# MiniBOT_New.net
KiCad netlist of a schematic drawn in EAGLE
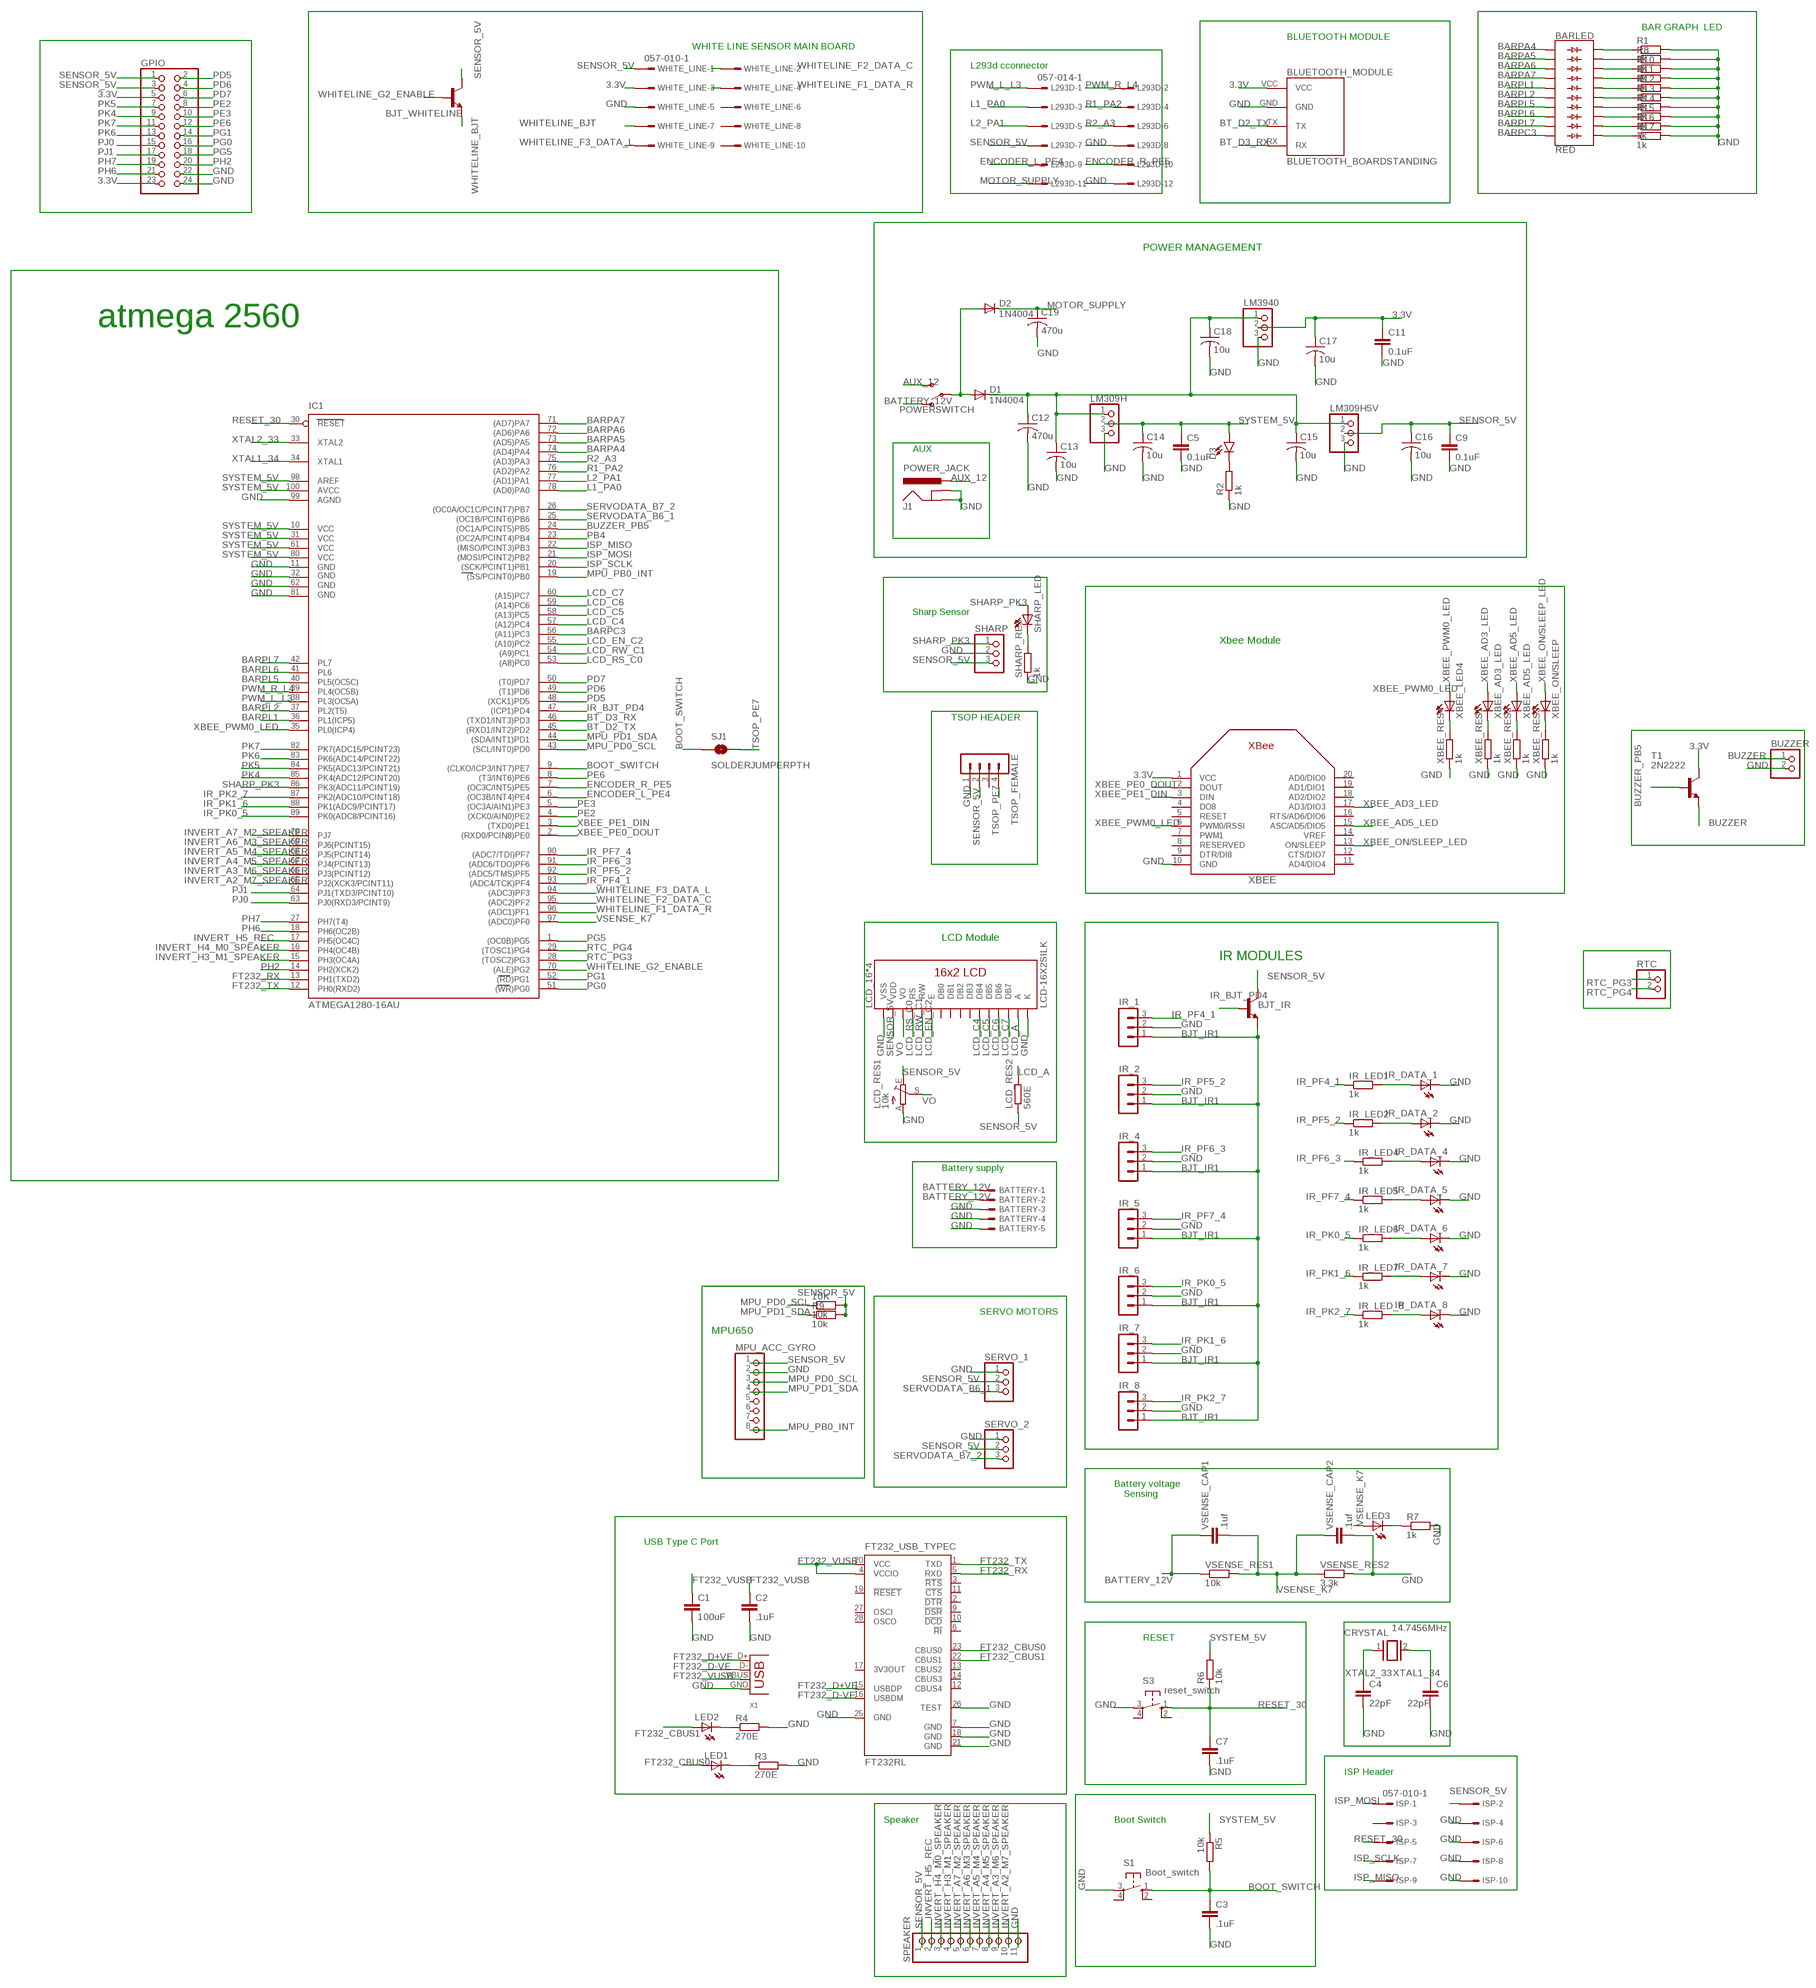
[diagram p0: schematic, sheet 1]

(export (version "E")
  (design (tool "Eeschema 10.0.6"))
  (components
    (comp (ref "10K")
      (value "10k")
      (footprint "eagle-import:R1206")
      (libsource (lib "eagle-import") (part "R-EU_R1206"))
    )
    (comp (ref "BARLED")
      (value "RED")
      (footprint "eagle-import:LED_BARGRAPH_10")
      (libsource (lib "eagle-import") (part "LED_BARGRAPH_10RED"))
    )
    (comp (ref "BATTERY")
      (value "KK-156-5")
      (footprint "eagle-import:KK-156-5")
      (libsource (lib "eagle-import") (part "KK-156-5"))
    )
    (comp (ref "BJT_IR")
      (value "2N2222")
      (footprint "eagle-import:TO92-EBC-OVAL")
      (libsource (lib "eagle-import") (part "2N2222"))
    )
    (comp (ref "BJT_WHITELINE")
      (value "2N2222")
      (footprint "eagle-import:TO92-EBC-OVAL")
      (libsource (lib "eagle-import") (part "2N2222"))
    )
    (comp (ref "BLUETOOTH_MODULE")
      (value "BLUETOOTH_BOARDSTANDING")
      (footprint "eagle-import:BT_BOARD_FOOTPRINT_STANDING")
      (libsource (lib "eagle-import") (part "BLUETOOTH_BOARDSTANDING"))
    )
    (comp (ref "BUZZER")
      (value "PINHD-1X2")
      (footprint "eagle-import:1X02")
      (libsource (lib "eagle-import") (part "PINHD-1X2"))
    )
    (comp (ref "C1")
      (value "100uF")
      (footprint "eagle-import:C1206")
      (libsource (lib "eagle-import") (part "C-EUC1206"))
    )
    (comp (ref "C2")
      (value ".1uF")
      (footprint "eagle-import:C1206")
      (libsource (lib "eagle-import") (part "C-EUC1206"))
    )
    (comp (ref "C3")
      (value ".1uF")
      (footprint "eagle-import:C1206")
      (libsource (lib "eagle-import") (part "C-EUC1206"))
    )
    (comp (ref "C4")
      (value "22pF")
      (footprint "eagle-import:C1206")
      (libsource (lib "eagle-import") (part "C-EUC1206"))
    )
    (comp (ref "C5")
      (value "0.1uF")
      (footprint "eagle-import:C1206")
      (libsource (lib "eagle-import") (part "C-EUC1206"))
    )
    (comp (ref "C6")
      (value "22pF")
      (footprint "eagle-import:C1206")
      (libsource (lib "eagle-import") (part "C-EUC1206"))
    )
    (comp (ref "C7")
      (value ".1uF")
      (footprint "eagle-import:C1206")
      (libsource (lib "eagle-import") (part "C-EUC1206"))
    )
    (comp (ref "C9")
      (value "0.1uF")
      (footprint "eagle-import:C1206")
      (libsource (lib "eagle-import") (part "C-EUC1206"))
    )
    (comp (ref "C11")
      (value "0.1uF")
      (footprint "eagle-import:C1206")
      (libsource (lib "eagle-import") (part "C-EUC1206"))
    )
    (comp (ref "C12")
      (value "470u")
      (footprint "eagle-import:C025-050X050")
      (libsource (lib "eagle-import") (part "C-US025-050X050"))
    )
    (comp (ref "C13")
      (value "10u")
      (footprint "eagle-import:C025-050X050")
      (libsource (lib "eagle-import") (part "C-US025-050X050"))
    )
    (comp (ref "C14")
      (value "10u")
      (footprint "eagle-import:C025-050X050")
      (libsource (lib "eagle-import") (part "C-US025-050X050"))
    )
    (comp (ref "C15")
      (value "10u")
      (footprint "eagle-import:C025-050X050")
      (libsource (lib "eagle-import") (part "C-US025-050X050"))
    )
    (comp (ref "C16")
      (value "10u")
      (footprint "eagle-import:C025-050X050")
      (libsource (lib "eagle-import") (part "C-US025-050X050"))
    )
    (comp (ref "C17")
      (value "10u")
      (footprint "eagle-import:C025-050X050")
      (libsource (lib "eagle-import") (part "C-US025-050X050"))
    )
    (comp (ref "C18")
      (value "10u")
      (footprint "eagle-import:C025-050X050")
      (libsource (lib "eagle-import") (part "C-US025-050X050"))
    )
    (comp (ref "C19")
      (value "470u")
      (footprint "eagle-import:C025-050X050")
      (libsource (lib "eagle-import") (part "C-US025-050X050"))
    )
    (comp (ref "CRYSTAL")
      (value "14.7456MHz")
      (footprint "eagle-import:QS")
      (libsource (lib "eagle-import") (part "XTAL/S"))
    )
    (comp (ref "D1")
      (value "1N4004")
      (footprint "eagle-import:DO41-10")
      (libsource (lib "eagle-import") (part "1N4004"))
    )
    (comp (ref "D2")
      (value "1N4004")
      (footprint "eagle-import:DO41-10")
      (libsource (lib "eagle-import") (part "1N4004"))
    )
    (comp (ref "D3")
      (value "LED1206")
      (footprint "eagle-import:LED-1206")
      (libsource (lib "eagle-import") (part "LED1206"))
    )
    (comp (ref "FT232_USB_TYPEC")
      (value "FT232RL")
      (footprint "eagle-import:SSOP28")
      (libsource (lib "eagle-import") (part "FT232RL"))
    )
    (comp (ref "GPIO")
      (value "PINHD-2X12")
      (footprint "eagle-import:2X12")
      (libsource (lib "eagle-import") (part "PINHD-2X12"))
    )
    (comp (ref "IC1")
      (value "ATMEGA1280-16AU")
      (footprint "eagle-import:TQFP100")
      (libsource (lib "eagle-import") (part "ATMEGAAU1280-16"))
    )
    (comp (ref "IR_1")
      (value "MA03-1")
      (footprint "eagle-import:MA03-1")
      (libsource (lib "eagle-import") (part "MA03-1"))
    )
    (comp (ref "IR_2")
      (value "MA03-1")
      (footprint "eagle-import:MA03-1")
      (libsource (lib "eagle-import") (part "MA03-1"))
    )
    (comp (ref "IR_4")
      (value "MA03-1")
      (footprint "eagle-import:MA03-1")
      (libsource (lib "eagle-import") (part "MA03-1"))
    )
    (comp (ref "IR_5")
      (value "MA03-1")
      (footprint "eagle-import:MA03-1")
      (libsource (lib "eagle-import") (part "MA03-1"))
    )
    (comp (ref "IR_6")
      (value "MA03-1")
      (footprint "eagle-import:MA03-1")
      (libsource (lib "eagle-import") (part "MA03-1"))
    )
    (comp (ref "IR_7")
      (value "MA03-1")
      (footprint "eagle-import:MA03-1")
      (libsource (lib "eagle-import") (part "MA03-1"))
    )
    (comp (ref "IR_8")
      (value "MA03-1")
      (footprint "eagle-import:MA03-1")
      (libsource (lib "eagle-import") (part "MA03-1"))
    )
    (comp (ref "IR_DATA_1")
      (value "LEDSMT1206")
      (footprint "eagle-import:1206")
      (libsource (lib "eagle-import") (part "LEDSMT1206"))
    )
    (comp (ref "IR_DATA_2")
      (value "LEDSMT1206")
      (footprint "eagle-import:1206")
      (libsource (lib "eagle-import") (part "LEDSMT1206"))
    )
    (comp (ref "IR_DATA_4")
      (value "LEDSMT1206")
      (footprint "eagle-import:1206")
      (libsource (lib "eagle-import") (part "LEDSMT1206"))
    )
    (comp (ref "IR_DATA_5")
      (value "LEDSMT1206")
      (footprint "eagle-import:1206")
      (libsource (lib "eagle-import") (part "LEDSMT1206"))
    )
    (comp (ref "IR_DATA_6")
      (value "LEDSMT1206")
      (footprint "eagle-import:1206")
      (libsource (lib "eagle-import") (part "LEDSMT1206"))
    )
    (comp (ref "IR_DATA_7")
      (value "LEDSMT1206")
      (footprint "eagle-import:1206")
      (libsource (lib "eagle-import") (part "LEDSMT1206"))
    )
    (comp (ref "IR_DATA_8")
      (value "LEDSMT1206")
      (footprint "eagle-import:1206")
      (libsource (lib "eagle-import") (part "LEDSMT1206"))
    )
    (comp (ref "IR_LED1")
      (value "1k")
      (footprint "eagle-import:R1206")
      (libsource (lib "eagle-import") (part "R-EU_R1206"))
    )
    (comp (ref "IR_LED2")
      (value "1k")
      (footprint "eagle-import:R1206")
      (libsource (lib "eagle-import") (part "R-EU_R1206"))
    )
    (comp (ref "IR_LED4")
      (value "1k")
      (footprint "eagle-import:R1206")
      (libsource (lib "eagle-import") (part "R-EU_R1206"))
    )
    (comp (ref "IR_LED5")
      (value "1k")
      (footprint "eagle-import:R1206")
      (libsource (lib "eagle-import") (part "R-EU_R1206"))
    )
    (comp (ref "IR_LED6")
      (value "1k")
      (footprint "eagle-import:R1206")
      (libsource (lib "eagle-import") (part "R-EU_R1206"))
    )
    (comp (ref "IR_LED7")
      (value "1k")
      (footprint "eagle-import:R1206")
      (libsource (lib "eagle-import") (part "R-EU_R1206"))
    )
    (comp (ref "IR_LED_8")
      (value "1k")
      (footprint "eagle-import:R1206")
      (libsource (lib "eagle-import") (part "R-EU_R1206"))
    )
    (comp (ref "ISP")
      (value "057-010-1")
      (footprint "eagle-import:057-010-1")
      (libsource (lib "eagle-import") (part "057-010-1"))
    )
    (comp (ref "J1")
      (value "POWER_JACK")
      (footprint "eagle-import:POWER_JACK_PTH")
      (libsource (lib "eagle-import") (part "POWER_JACK"))
    )
    (comp (ref "L293D")
      (value "057-014-1")
      (footprint "eagle-import:057-014-1")
      (libsource (lib "eagle-import") (part "057-014-1"))
    )
    (comp (ref "LCD_16*4")
      (value "LCD-16X2SILK")
      (footprint "eagle-import:LCD-16X2")
      (libsource (lib "eagle-import") (part "LCD-16X2SILK"))
    )
    (comp (ref "LCD_RES1")
      (value "10k")
      (footprint "eagle-import:CA6V")
      (libsource (lib "eagle-import") (part "TRIM_EU-CA6V"))
    )
    (comp (ref "LCD_RES2")
      (value "560E")
      (footprint "eagle-import:R1206")
      (libsource (lib "eagle-import") (part "R-EU_R1206"))
    )
    (comp (ref "LED1")
      (value "LEDSMT1206")
      (footprint "eagle-import:1206")
      (libsource (lib "eagle-import") (part "LEDSMT1206"))
    )
    (comp (ref "LED2")
      (value "LEDSMT1206")
      (footprint "eagle-import:1206")
      (libsource (lib "eagle-import") (part "LEDSMT1206"))
    )
    (comp (ref "LED3")
      (value "LEDSMT1206")
      (footprint "eagle-import:1206")
      (libsource (lib "eagle-import") (part "LEDSMT1206"))
    )
    (comp (ref "LM309H")
      (value "PINHD-1X3")
      (footprint "eagle-import:1X03")
      (libsource (lib "eagle-import") (part "PINHD-1X3"))
    )
    (comp (ref "LM309H5V")
      (value "PINHD-1X3")
      (footprint "eagle-import:1X03")
      (libsource (lib "eagle-import") (part "PINHD-1X3"))
    )
    (comp (ref "LM3940")
      (value "PINHD-1X3")
      (footprint "eagle-import:1X03")
      (libsource (lib "eagle-import") (part "PINHD-1X3"))
    )
    (comp (ref "MPU_ACC_GYRO")
      (value "PINHD-1X8")
      (footprint "eagle-import:1X08")
      (libsource (lib "eagle-import") (part "PINHD-1X8"))
    )
    (comp (ref "POWERSWITCH")
      (value "SWITCH-SPDT-PTH-11.6X4.0MM-LOCK")
      (footprint "eagle-import:SWITCH_SPDT_PTH_11.6X4.0MM_LOCK")
      (libsource (lib "eagle-import") (part "SWITCH-SPDT-PTH-11.6X4.0MM-LOCK"))
    )
    (comp (ref "R1")
      (value "1k")
      (footprint "eagle-import:R1206")
      (libsource (lib "eagle-import") (part "R-EU_R1206"))
    )
    (comp (ref "R2")
      (value "1k")
      (footprint "eagle-import:R1206")
      (libsource (lib "eagle-import") (part "R-EU_R1206"))
    )
    (comp (ref "R3")
      (value "270E")
      (footprint "eagle-import:R1206")
      (libsource (lib "eagle-import") (part "R-EU_R1206"))
    )
    (comp (ref "R4")
      (value "270E")
      (footprint "eagle-import:R1206")
      (libsource (lib "eagle-import") (part "R-EU_R1206"))
    )
    (comp (ref "R5")
      (value "10k")
      (footprint "eagle-import:R1206")
      (libsource (lib "eagle-import") (part "R-EU_R1206"))
    )
    (comp (ref "R6")
      (value "10k")
      (footprint "eagle-import:R1206")
      (libsource (lib "eagle-import") (part "R-EU_R1206"))
    )
    (comp (ref "R7")
      (value "1k")
      (footprint "eagle-import:R1206")
      (libsource (lib "eagle-import") (part "R-EU_R1206"))
    )
    (comp (ref "R8")
      (value "1k")
      (footprint "eagle-import:R1206")
      (libsource (lib "eagle-import") (part "R-EU_R1206"))
    )
    (comp (ref "R9")
      (value "10k")
      (footprint "eagle-import:R1206")
      (libsource (lib "eagle-import") (part "R-EU_R1206"))
    )
    (comp (ref "R10")
      (value "1k")
      (footprint "eagle-import:R1206")
      (libsource (lib "eagle-import") (part "R-EU_R1206"))
    )
    (comp (ref "R11")
      (value "1k")
      (footprint "eagle-import:R1206")
      (libsource (lib "eagle-import") (part "R-EU_R1206"))
    )
    (comp (ref "R12")
      (value "1k")
      (footprint "eagle-import:R1206")
      (libsource (lib "eagle-import") (part "R-EU_R1206"))
    )
    (comp (ref "R13")
      (value "1k")
      (footprint "eagle-import:R1206")
      (libsource (lib "eagle-import") (part "R-EU_R1206"))
    )
    (comp (ref "R14")
      (value "1k")
      (footprint "eagle-import:R1206")
      (libsource (lib "eagle-import") (part "R-EU_R1206"))
    )
    (comp (ref "R15")
      (value "1k")
      (footprint "eagle-import:R1206")
      (libsource (lib "eagle-import") (part "R-EU_R1206"))
    )
    (comp (ref "R16")
      (value "1k")
      (footprint "eagle-import:R1206")
      (libsource (lib "eagle-import") (part "R-EU_R1206"))
    )
    (comp (ref "R17")
      (value "1k")
      (footprint "eagle-import:R1206")
      (libsource (lib "eagle-import") (part "R-EU_R1206"))
    )
    (comp (ref "RTC")
      (value "PINHD-1X2")
      (footprint "eagle-import:1X02")
      (libsource (lib "eagle-import") (part "PINHD-1X2"))
    )
    (comp (ref "S1")
      (value "Boot_switch")
      (footprint "eagle-import:B3F-10XX")
      (fields (field (name "MPN") "B3F-1000"))
      (libsource (lib "eagle-import") (part "10-XX"))
    )
    (comp (ref "S3")
      (value "reset_switch")
      (footprint "eagle-import:B3F-10XX")
      (fields (field (name "MPN") "B3F-1000"))
      (libsource (lib "eagle-import") (part "10-XX"))
    )
    (comp (ref "SERVO_1")
      (value "PINHD-1X3")
      (footprint "eagle-import:1X03")
      (libsource (lib "eagle-import") (part "pinhead_325_PINHD-1X3"))
    )
    (comp (ref "SERVO_2")
      (value "PINHD-1X3")
      (footprint "eagle-import:1X03")
      (libsource (lib "eagle-import") (part "pinhead_325_PINHD-1X3"))
    )
    (comp (ref "SHARP")
      (value "PINHD-1X3")
      (footprint "eagle-import:1X03")
      (libsource (lib "eagle-import") (part "pinhead_325_PINHD-1X3"))
    )
    (comp (ref "SHARP_LED")
      (value "LEDSMT1206")
      (footprint "eagle-import:1206")
      (libsource (lib "eagle-import") (part "LEDSMT1206"))
    )
    (comp (ref "SHARP_RES")
      (value "1k")
      (footprint "eagle-import:R1206")
      (libsource (lib "eagle-import") (part "R-EU_R1206"))
    )
    (comp (ref "SJ1")
      (value "SOLDERJUMPERPTH")
      (footprint "eagle-import:SJ_2S-PTH")
      (libsource (lib "eagle-import") (part "SOLDERJUMPERPTH"))
    )
    (comp (ref "SPEAKER")
      (value "PINHD-1X11")
      (footprint "eagle-import:1X11")
      (libsource (lib "eagle-import") (part "PINHD-1X11"))
    )
    (comp (ref "T1")
      (value "2N2222")
      (footprint "eagle-import:TO92-EBC-OVAL")
      (libsource (lib "eagle-import") (part "2N2222"))
    )
    (comp (ref "TSOP_FEMALE")
      (value "MA04-1")
      (footprint "eagle-import:MA04-1")
      (libsource (lib "eagle-import") (part "MA04-1"))
    )
    (comp (ref "VSENSE_CAP1")
      (value ".1uf")
      (footprint "eagle-import:C1206")
      (libsource (lib "eagle-import") (part "C-EUC1206"))
    )
    (comp (ref "VSENSE_CAP2")
      (value ".1uf")
      (footprint "eagle-import:C1206")
      (libsource (lib "eagle-import") (part "C-EUC1206"))
    )
    (comp (ref "VSENSE_RES1")
      (value "10k")
      (footprint "eagle-import:R1206")
      (libsource (lib "eagle-import") (part "R-EU_R1206"))
    )
    (comp (ref "VSENSE_RES2")
      (value "3.3k")
      (footprint "eagle-import:R1206")
      (libsource (lib "eagle-import") (part "R-EU_R1206"))
    )
    (comp (ref "WHITE_LINE")
      (value "057-010-1")
      (footprint "eagle-import:057-010-1")
      (libsource (lib "eagle-import") (part "057-010-1"))
    )
    (comp (ref "X1")
      (value "USB-B-H")
      (footprint "eagle-import:USB-B-H")
      (libsource (lib "eagle-import") (part "USB-B-H"))
    )
    (comp (ref "XBEE")
      (value "XBEE")
      (footprint "eagle-import:XBEE")
      (libsource (lib "eagle-import") (part "XBEE"))
    )
    (comp (ref "XBEE_AD3_LED")
      (value "LEDSMT1206")
      (footprint "eagle-import:1206")
      (libsource (lib "eagle-import") (part "LEDSMT1206"))
    )
    (comp (ref "XBEE_AD5_LED")
      (value "LEDSMT1206")
      (footprint "eagle-import:1206")
      (libsource (lib "eagle-import") (part "LEDSMT1206"))
    )
    (comp (ref "XBEE_LED4")
      (value "LEDSMT1206")
      (footprint "eagle-import:1206")
      (libsource (lib "eagle-import") (part "LEDSMT1206"))
    )
    (comp (ref "XBEE_ON/SLEEP")
      (value "LEDSMT1206")
      (footprint "eagle-import:1206")
      (libsource (lib "eagle-import") (part "LEDSMT1206"))
    )
    (comp (ref "XBEE_RES1")
      (value "1k")
      (footprint "eagle-import:M1206")
      (libsource (lib "eagle-import") (part "R-EU_M1206"))
    )
    (comp (ref "XBEE_RES2")
      (value "1k")
      (footprint "eagle-import:M1206")
      (libsource (lib "eagle-import") (part "R-EU_M1206"))
    )
    (comp (ref "XBEE_RES3")
      (value "1k")
      (footprint "eagle-import:M1206")
      (libsource (lib "eagle-import") (part "R-EU_M1206"))
    )
    (comp (ref "XBEE_RES4")
      (value "1k")
      (footprint "eagle-import:M1206")
      (libsource (lib "eagle-import") (part "R-EU_M1206"))
    )
  )
  (nets
    (net (code "1") (name "/3.3V") (class "Default")
      (node (ref "BLUETOOTH_MODULE") (pin "VCC") (pinfunction "VCC_VCC") (pintype "bidirectional"))
      (node (ref "C11") (pin "1") (pinfunction "1_1") (pintype "passive"))
      (node (ref "C17") (pin "1") (pinfunction "1_1") (pintype "passive"))
      (node (ref "GPIO") (pin "23") (pinfunction "23_23") (pintype "passive"))
      (node (ref "GPIO") (pin "5") (pinfunction "5_5") (pintype "passive"))
      (node (ref "LM3940") (pin "2") (pinfunction "2_2") (pintype "passive"))
      (node (ref "T1") (pin "C") (pinfunction "C_C") (pintype "passive"))
      (node (ref "WHITE_LINE") (pin "3") (pinfunction "S_3") (pintype "passive"))
      (node (ref "XBEE") (pin "1") (pinfunction "VCC_1") (pintype "power_in"))
    )
    (net (code "2") (name "/AUX_12") (class "Default")
      (node (ref "J1") (pin "PWR") (pinfunction "PWR_PWR") (pintype "bidirectional"))
      (node (ref "POWERSWITCH") (pin "3") (pinfunction "S_3") (pintype "passive"))
    )
    (net (code "3") (name "/BARPA4") (class "Default")
      (node (ref "BARLED") (pin "1") (pinfunction "A_1") (pintype "passive"))
      (node (ref "IC1") (pin "74") (pinfunction "(AD4)PA4_74") (pintype "bidirectional"))
    )
    (net (code "4") (name "/BARPA5") (class "Default")
      (node (ref "BARLED") (pin "2") (pinfunction "A1_2") (pintype "passive"))
      (node (ref "IC1") (pin "73") (pinfunction "(AD5)PA5_73") (pintype "bidirectional"))
    )
    (net (code "5") (name "/BARPA6") (class "Default")
      (node (ref "BARLED") (pin "3") (pinfunction "A2_3") (pintype "passive"))
      (node (ref "IC1") (pin "72") (pinfunction "(AD6)PA6_72") (pintype "bidirectional"))
    )
    (net (code "6") (name "/BARPA7") (class "Default")
      (node (ref "BARLED") (pin "4") (pinfunction "A3_4") (pintype "passive"))
      (node (ref "IC1") (pin "71") (pinfunction "(AD7)PA7_71") (pintype "bidirectional"))
    )
    (net (code "7") (name "/BARPC3") (class "Default")
      (node (ref "BARLED") (pin "10") (pinfunction "A9_10") (pintype "passive"))
      (node (ref "IC1") (pin "56") (pinfunction "(A11)PC3_56") (pintype "bidirectional"))
    )
    (net (code "8") (name "/BARPL1") (class "Default")
      (node (ref "BARLED") (pin "5") (pinfunction "A4_5") (pintype "passive"))
      (node (ref "IC1") (pin "36") (pinfunction "PL1(ICP5)_36") (pintype "bidirectional"))
    )
    (net (code "9") (name "/BARPL2") (class "Default")
      (node (ref "BARLED") (pin "6") (pinfunction "A5_6") (pintype "passive"))
      (node (ref "IC1") (pin "37") (pinfunction "PL2(T5)_37") (pintype "bidirectional"))
    )
    (net (code "10") (name "/BARPL5") (class "Default")
      (node (ref "BARLED") (pin "7") (pinfunction "A6_7") (pintype "passive"))
      (node (ref "IC1") (pin "40") (pinfunction "PL5(OC5C)_40") (pintype "bidirectional"))
    )
    (net (code "11") (name "/BARPL6") (class "Default")
      (node (ref "BARLED") (pin "8") (pinfunction "A7_8") (pintype "passive"))
      (node (ref "IC1") (pin "41") (pinfunction "PL6_41") (pintype "bidirectional"))
    )
    (net (code "12") (name "/BARPL7") (class "Default")
      (node (ref "BARLED") (pin "9") (pinfunction "A8_9") (pintype "passive"))
      (node (ref "IC1") (pin "42") (pinfunction "PL7_42") (pintype "bidirectional"))
    )
    (net (code "13") (name "/BATTERY_12V") (class "Default")
      (node (ref "BATTERY") (pin "1") (pinfunction "S_1") (pintype "passive"))
      (node (ref "BATTERY") (pin "2") (pinfunction "S_2") (pintype "passive"))
      (node (ref "POWERSWITCH") (pin "1") (pinfunction "O_1") (pintype "passive"))
      (node (ref "VSENSE_CAP1") (pin "1") (pinfunction "1_1") (pintype "passive"))
      (node (ref "VSENSE_RES1") (pin "1") (pinfunction "1_1") (pintype "passive"))
    )
    (net (code "14") (name "/BJT_IR1") (class "Default")
      (node (ref "BJT_IR") (pin "E") (pinfunction "E_E") (pintype "passive"))
      (node (ref "IR_1") (pin "1") (pinfunction "1_1") (pintype "passive"))
      (node (ref "IR_2") (pin "1") (pinfunction "1_1") (pintype "passive"))
      (node (ref "IR_4") (pin "1") (pinfunction "1_1") (pintype "passive"))
      (node (ref "IR_5") (pin "1") (pinfunction "1_1") (pintype "passive"))
      (node (ref "IR_6") (pin "1") (pinfunction "1_1") (pintype "passive"))
      (node (ref "IR_7") (pin "1") (pinfunction "1_1") (pintype "passive"))
      (node (ref "IR_8") (pin "1") (pinfunction "1_1") (pintype "passive"))
    )
    (net (code "15") (name "/BOOT_SWITCH") (class "Default")
      (node (ref "C3") (pin "1") (pinfunction "1_1") (pintype "passive"))
      (node (ref "IC1") (pin "9") (pinfunction "(CLKO/ICP3/INT7)PE7_9") (pintype "bidirectional"))
      (node (ref "R5") (pin "2") (pinfunction "2_2") (pintype "passive"))
      (node (ref "S1") (pin "1") (pinfunction "S_1") (pintype "passive"))
      (node (ref "SJ1") (pin "1") (pinfunction "1_1") (pintype "passive"))
    )
    (net (code "16") (name "/BT_D2_TX") (class "Default")
      (node (ref "BLUETOOTH_MODULE") (pin "TX") (pinfunction "TX_TX") (pintype "bidirectional"))
      (node (ref "IC1") (pin "45") (pinfunction "(RXD1/INT2)PD2_45") (pintype "bidirectional"))
    )
    (net (code "17") (name "/BT_D3_RX") (class "Default")
      (node (ref "BLUETOOTH_MODULE") (pin "RX") (pinfunction "RX_RX") (pintype "bidirectional"))
      (node (ref "IC1") (pin "46") (pinfunction "(TXD1/INT3)PD3_46") (pintype "bidirectional"))
    )
    (net (code "18") (name "/BUZZER") (class "Default")
      (node (ref "BUZZER") (pin "1") (pinfunction "1_1") (pintype "passive"))
      (node (ref "T1") (pin "E") (pinfunction "E_E") (pintype "passive"))
    )
    (net (code "19") (name "/BUZZER_PB5") (class "Default")
      (node (ref "IC1") (pin "24") (pinfunction "(OC1A/PCINT5)PB5_24") (pintype "bidirectional"))
      (node (ref "T1") (pin "B") (pinfunction "B_B") (pintype "passive"))
    )
    (net (code "20") (name "/ENCODER_L_PE4") (class "Default")
      (node (ref "IC1") (pin "6") (pinfunction "(OC3B/INT4)PE4_6") (pintype "bidirectional"))
      (node (ref "L293D") (pin "9") (pinfunction "S_9") (pintype "passive"))
    )
    (net (code "21") (name "/ENCODER_R_PE5") (class "Default")
      (node (ref "IC1") (pin "7") (pinfunction "(OC3C/INT5)PE5_7") (pintype "bidirectional"))
      (node (ref "L293D") (pin "10") (pinfunction "S_10") (pintype "passive"))
    )
    (net (code "22") (name "/FT232_CBUS0") (class "Default")
      (node (ref "FT232_USB_TYPEC") (pin "23") (pinfunction "CBUS0_23") (pintype "bidirectional"))
      (node (ref "LED1") (pin "A") (pinfunction "A_A") (pintype "passive"))
    )
    (net (code "23") (name "/FT232_CBUS1") (class "Default")
      (node (ref "FT232_USB_TYPEC") (pin "22") (pinfunction "CBUS1_22") (pintype "bidirectional"))
      (node (ref "LED2") (pin "A") (pinfunction "A_A") (pintype "passive"))
    )
    (net (code "24") (name "/FT232_D+VE") (class "Default")
      (node (ref "FT232_USB_TYPEC") (pin "15") (pinfunction "USBDP_15") (pintype "bidirectional"))
      (node (ref "X1") (pin "D+") (pinfunction "D+_D+") (pintype "bidirectional"))
    )
    (net (code "25") (name "/FT232_D-VE") (class "Default")
      (node (ref "FT232_USB_TYPEC") (pin "16") (pinfunction "USBDM_16") (pintype "bidirectional"))
      (node (ref "X1") (pin "D-") (pinfunction "D-_D-") (pintype "bidirectional"))
    )
    (net (code "26") (name "/FT232_RX") (class "Default")
      (node (ref "FT232_USB_TYPEC") (pin "5") (pinfunction "RXD_5") (pintype "input"))
      (node (ref "IC1") (pin "13") (pinfunction "PH1(TXD2)_13") (pintype "bidirectional"))
    )
    (net (code "27") (name "/FT232_TX") (class "Default")
      (node (ref "FT232_USB_TYPEC") (pin "1") (pinfunction "TXD_1") (pintype "output"))
      (node (ref "IC1") (pin "12") (pinfunction "PH0(RXD2)_12") (pintype "bidirectional"))
    )
    (net (code "28") (name "/FT232_VUSB") (class "Default")
      (node (ref "C1") (pin "1") (pinfunction "1_1") (pintype "passive"))
      (node (ref "C2") (pin "1") (pinfunction "1_1") (pintype "passive"))
      (node (ref "FT232_USB_TYPEC") (pin "20") (pinfunction "VCC_20") (pintype "power_in"))
      (node (ref "FT232_USB_TYPEC") (pin "4") (pinfunction "VCCIO_4") (pintype "power_in"))
      (node (ref "X1") (pin "VBUS") (pinfunction "VBUS_VBUS") (pintype "bidirectional"))
    )
    (net (code "29") (name "/GND") (class "Default")
      (node (ref "BATTERY") (pin "3") (pinfunction "S_3") (pintype "passive"))
      (node (ref "BATTERY") (pin "4") (pinfunction "S_4") (pintype "passive"))
      (node (ref "BATTERY") (pin "5") (pinfunction "S_5") (pintype "passive"))
      (node (ref "BLUETOOTH_MODULE") (pin "GND") (pinfunction "GND_GND") (pintype "bidirectional"))
      (node (ref "BUZZER") (pin "2") (pinfunction "2_2") (pintype "passive"))
      (node (ref "C1") (pin "2") (pinfunction "2_2") (pintype "passive"))
      (node (ref "C11") (pin "2") (pinfunction "2_2") (pintype "passive"))
      (node (ref "C12") (pin "2") (pinfunction "2_2") (pintype "passive"))
      (node (ref "C13") (pin "2") (pinfunction "2_2") (pintype "passive"))
      (node (ref "C14") (pin "2") (pinfunction "2_2") (pintype "passive"))
      (node (ref "C15") (pin "2") (pinfunction "2_2") (pintype "passive"))
      (node (ref "C16") (pin "2") (pinfunction "2_2") (pintype "passive"))
      (node (ref "C17") (pin "2") (pinfunction "2_2") (pintype "passive"))
      (node (ref "C18") (pin "2") (pinfunction "2_2") (pintype "passive"))
      (node (ref "C19") (pin "2") (pinfunction "2_2") (pintype "passive"))
      (node (ref "C2") (pin "2") (pinfunction "2_2") (pintype "passive"))
      (node (ref "C3") (pin "2") (pinfunction "2_2") (pintype "passive"))
      (node (ref "C4") (pin "2") (pinfunction "2_2") (pintype "passive"))
      (node (ref "C5") (pin "2") (pinfunction "2_2") (pintype "passive"))
      (node (ref "C6") (pin "2") (pinfunction "2_2") (pintype "passive"))
      (node (ref "C7") (pin "2") (pinfunction "2_2") (pintype "passive"))
      (node (ref "C9") (pin "2") (pinfunction "2_2") (pintype "passive"))
      (node (ref "FT232_USB_TYPEC") (pin "18") (pinfunction "GND_18") (pintype "power_in"))
      (node (ref "FT232_USB_TYPEC") (pin "21") (pinfunction "GND_21") (pintype "power_in"))
      (node (ref "FT232_USB_TYPEC") (pin "25") (pinfunction "GND_25") (pintype "power_in"))
      (node (ref "FT232_USB_TYPEC") (pin "26") (pinfunction "TEST_26") (pintype "input"))
      (node (ref "FT232_USB_TYPEC") (pin "7") (pinfunction "GND_7") (pintype "power_in"))
      (node (ref "GPIO") (pin "22") (pinfunction "22_22") (pintype "passive"))
      (node (ref "GPIO") (pin "24") (pinfunction "24_24") (pintype "passive"))
      (node (ref "IC1") (pin "11") (pinfunction "GND_11") (pintype "power_in"))
      (node (ref "IC1") (pin "32") (pinfunction "GND1_32") (pintype "power_in"))
      (node (ref "IC1") (pin "62") (pinfunction "GND2_62") (pintype "power_in"))
      (node (ref "IC1") (pin "81") (pinfunction "GND3_81") (pintype "power_in"))
      (node (ref "IC1") (pin "99") (pinfunction "AGND_99") (pintype "power_in"))
      (node (ref "IR_1") (pin "2") (pinfunction "2_2") (pintype "passive"))
      (node (ref "IR_2") (pin "2") (pinfunction "2_2") (pintype "passive"))
      (node (ref "IR_4") (pin "2") (pinfunction "2_2") (pintype "passive"))
      (node (ref "IR_5") (pin "2") (pinfunction "2_2") (pintype "passive"))
      (node (ref "IR_6") (pin "2") (pinfunction "2_2") (pintype "passive"))
      (node (ref "IR_7") (pin "2") (pinfunction "2_2") (pintype "passive"))
      (node (ref "IR_8") (pin "2") (pinfunction "2_2") (pintype "passive"))
      (node (ref "IR_DATA_1") (pin "C") (pinfunction "C_C") (pintype "passive"))
      (node (ref "IR_DATA_2") (pin "C") (pinfunction "C_C") (pintype "passive"))
      (node (ref "IR_DATA_4") (pin "C") (pinfunction "C_C") (pintype "passive"))
      (node (ref "IR_DATA_5") (pin "C") (pinfunction "C_C") (pintype "passive"))
      (node (ref "IR_DATA_6") (pin "C") (pinfunction "C_C") (pintype "passive"))
      (node (ref "IR_DATA_7") (pin "C") (pinfunction "C_C") (pintype "passive"))
      (node (ref "IR_DATA_8") (pin "C") (pinfunction "C_C") (pintype "passive"))
      (node (ref "ISP") (pin "10") (pinfunction "S_10") (pintype "passive"))
      (node (ref "ISP") (pin "4") (pinfunction "S_4") (pintype "passive"))
      (node (ref "ISP") (pin "6") (pinfunction "S_6") (pintype "passive"))
      (node (ref "ISP") (pin "8") (pinfunction "S_8") (pintype "passive"))
      (node (ref "J1") (pin "GND") (pinfunction "GND_GND") (pintype "bidirectional"))
      (node (ref "J1") (pin "GNDBREAK") (pinfunction "GNDBREAK_GNDBREAK") (pintype "bidirectional"))
      (node (ref "L293D") (pin "12") (pinfunction "S_12") (pintype "passive"))
      (node (ref "L293D") (pin "8") (pinfunction "S_8") (pintype "passive"))
      (node (ref "LCD_16*4") (pin "1") (pinfunction "VSS_1") (pintype "power_in"))
      (node (ref "LCD_16*4") (pin "16") (pinfunction "K_16") (pintype "power_in"))
      (node (ref "LCD_RES1") (pin "A") (pinfunction "A_A") (pintype "passive"))
      (node (ref "LM309H") (pin "3") (pinfunction "3_3") (pintype "passive"))
      (node (ref "LM309H5V") (pin "3") (pinfunction "3_3") (pintype "passive"))
      (node (ref "LM3940") (pin "3") (pinfunction "3_3") (pintype "passive"))
      (node (ref "MPU_ACC_GYRO") (pin "2") (pinfunction "2_2") (pintype "passive"))
      (node (ref "R1") (pin "2") (pinfunction "2_2") (pintype "passive"))
      (node (ref "R10") (pin "2") (pinfunction "2_2") (pintype "passive"))
      (node (ref "R11") (pin "2") (pinfunction "2_2") (pintype "passive"))
      (node (ref "R12") (pin "2") (pinfunction "2_2") (pintype "passive"))
      (node (ref "R13") (pin "2") (pinfunction "2_2") (pintype "passive"))
      (node (ref "R14") (pin "2") (pinfunction "2_2") (pintype "passive"))
      (node (ref "R15") (pin "2") (pinfunction "2_2") (pintype "passive"))
      (node (ref "R16") (pin "2") (pinfunction "2_2") (pintype "passive"))
      (node (ref "R17") (pin "2") (pinfunction "2_2") (pintype "passive"))
      (node (ref "R2") (pin "1") (pinfunction "1_1") (pintype "passive"))
      (node (ref "R3") (pin "2") (pinfunction "2_2") (pintype "passive"))
      (node (ref "R4") (pin "2") (pinfunction "2_2") (pintype "passive"))
      (node (ref "R7") (pin "2") (pinfunction "2_2") (pintype "passive"))
      (node (ref "R8") (pin "2") (pinfunction "2_2") (pintype "passive"))
      (node (ref "S1") (pin "3") (pinfunction "P_3") (pintype "passive"))
      (node (ref "S3") (pin "3") (pinfunction "P_3") (pintype "passive"))
      (node (ref "SERVO_1") (pin "1") (pinfunction "1_1") (pintype "passive"))
      (node (ref "SERVO_2") (pin "1") (pinfunction "1_1") (pintype "passive"))
      (node (ref "SHARP") (pin "2") (pinfunction "2_2") (pintype "passive"))
      (node (ref "SHARP_RES") (pin "1") (pinfunction "1_1") (pintype "passive"))
      (node (ref "SPEAKER") (pin "11") (pinfunction "11_11") (pintype "passive"))
      (node (ref "TSOP_FEMALE") (pin "1") (pinfunction "1_1") (pintype "passive"))
      (node (ref "VSENSE_CAP2") (pin "2") (pinfunction "2_2") (pintype "passive"))
      (node (ref "VSENSE_RES2") (pin "2") (pinfunction "2_2") (pintype "passive"))
      (node (ref "WHITE_LINE") (pin "5") (pinfunction "S_5") (pintype "passive"))
      (node (ref "X1") (pin "GND") (pinfunction "GND_GND") (pintype "bidirectional"))
      (node (ref "XBEE") (pin "10") (pinfunction "GND_10") (pintype "power_in"))
      (node (ref "XBEE_RES1") (pin "1") (pinfunction "1_1") (pintype "passive"))
      (node (ref "XBEE_RES2") (pin "1") (pinfunction "1_1") (pintype "passive"))
      (node (ref "XBEE_RES3") (pin "1") (pinfunction "1_1") (pintype "passive"))
      (node (ref "XBEE_RES4") (pin "1") (pinfunction "1_1") (pintype "passive"))
    )
    (net (code "30") (name "/INVERT_A2_M7_SPEAKER") (class "Default")
      (node (ref "IC1") (pin "65") (pinfunction "PJ2(XCK3/PCINT11)_65") (pintype "bidirectional"))
      (node (ref "SPEAKER") (pin "10") (pinfunction "10_10") (pintype "passive"))
    )
    (net (code "31") (name "/INVERT_A3_M6_SPEAKER") (class "Default")
      (node (ref "IC1") (pin "66") (pinfunction "PJ3(PCINT12)_66") (pintype "bidirectional"))
      (node (ref "SPEAKER") (pin "9") (pinfunction "9_9") (pintype "passive"))
    )
    (net (code "32") (name "/INVERT_A4_M5_SPEAKER") (class "Default")
      (node (ref "IC1") (pin "67") (pinfunction "PJ4(PCINT13)_67") (pintype "bidirectional"))
      (node (ref "SPEAKER") (pin "8") (pinfunction "8_8") (pintype "passive"))
    )
    (net (code "33") (name "/INVERT_A5_M4_SPEAKER") (class "Default")
      (node (ref "IC1") (pin "68") (pinfunction "PJ5(PCINT14)_68") (pintype "bidirectional"))
      (node (ref "SPEAKER") (pin "7") (pinfunction "7_7") (pintype "passive"))
    )
    (net (code "34") (name "/INVERT_A6_M3_SPEAKER") (class "Default")
      (node (ref "IC1") (pin "69") (pinfunction "PJ6(PCINT15)_69") (pintype "bidirectional"))
      (node (ref "SPEAKER") (pin "6") (pinfunction "6_6") (pintype "passive"))
    )
    (net (code "35") (name "/INVERT_A7_M2_SPEAKER") (class "Default")
      (node (ref "IC1") (pin "79") (pinfunction "PJ7_79") (pintype "bidirectional"))
      (node (ref "SPEAKER") (pin "5") (pinfunction "5_5") (pintype "passive"))
    )
    (net (code "36") (name "/INVERT_H3_M1_SPEAKER") (class "Default")
      (node (ref "IC1") (pin "15") (pinfunction "PH3(OC4A)_15") (pintype "bidirectional"))
      (node (ref "SPEAKER") (pin "4") (pinfunction "4_4") (pintype "passive"))
    )
    (net (code "37") (name "/INVERT_H4_M0_SPEAKER") (class "Default")
      (node (ref "IC1") (pin "16") (pinfunction "PH4(OC4B)_16") (pintype "bidirectional"))
      (node (ref "SPEAKER") (pin "3") (pinfunction "3_3") (pintype "passive"))
    )
    (net (code "38") (name "/INVERT_H5_REC") (class "Default")
      (node (ref "IC1") (pin "17") (pinfunction "PH5(OC4C)_17") (pintype "bidirectional"))
      (node (ref "SPEAKER") (pin "2") (pinfunction "2_2") (pintype "passive"))
    )
    (net (code "39") (name "/IR_BJT_PD4") (class "Default")
      (node (ref "BJT_IR") (pin "B") (pinfunction "B_B") (pintype "passive"))
      (node (ref "IC1") (pin "47") (pinfunction "(ICP1)PD4_47") (pintype "bidirectional"))
    )
    (net (code "40") (name "/IR_PF4_1") (class "Default")
      (node (ref "IC1") (pin "93") (pinfunction "(ADC4/TCK)PF4_93") (pintype "bidirectional"))
      (node (ref "IR_1") (pin "3") (pinfunction "3_3") (pintype "passive"))
      (node (ref "IR_LED1") (pin "1") (pinfunction "1_1") (pintype "passive"))
    )
    (net (code "41") (name "/IR_PF5_2") (class "Default")
      (node (ref "IC1") (pin "92") (pinfunction "(ADC5/TMS)PF5_92") (pintype "bidirectional"))
      (node (ref "IR_2") (pin "3") (pinfunction "3_3") (pintype "passive"))
      (node (ref "IR_LED2") (pin "1") (pinfunction "1_1") (pintype "passive"))
    )
    (net (code "42") (name "/IR_PF6_3") (class "Default")
      (node (ref "IC1") (pin "91") (pinfunction "(ADC6/TDO)PF6_91") (pintype "bidirectional"))
      (node (ref "IR_4") (pin "3") (pinfunction "3_3") (pintype "passive"))
      (node (ref "IR_LED4") (pin "1") (pinfunction "1_1") (pintype "passive"))
    )
    (net (code "43") (name "/IR_PF7_4") (class "Default")
      (node (ref "IC1") (pin "90") (pinfunction "(ADC7/TDI)PF7_90") (pintype "bidirectional"))
      (node (ref "IR_5") (pin "3") (pinfunction "3_3") (pintype "passive"))
      (node (ref "IR_LED5") (pin "1") (pinfunction "1_1") (pintype "passive"))
    )
    (net (code "44") (name "/IR_PK0_5") (class "Default")
      (node (ref "IC1") (pin "89") (pinfunction "PK0(ADC8/PCINT16)_89") (pintype "bidirectional"))
      (node (ref "IR_6") (pin "3") (pinfunction "3_3") (pintype "passive"))
      (node (ref "IR_LED6") (pin "1") (pinfunction "1_1") (pintype "passive"))
    )
    (net (code "45") (name "/IR_PK1_6") (class "Default")
      (node (ref "IC1") (pin "88") (pinfunction "PK1(ADC9/PCINT17)_88") (pintype "bidirectional"))
      (node (ref "IR_7") (pin "3") (pinfunction "3_3") (pintype "passive"))
      (node (ref "IR_LED7") (pin "1") (pinfunction "1_1") (pintype "passive"))
    )
    (net (code "46") (name "/IR_PK2_7") (class "Default")
      (node (ref "IC1") (pin "87") (pinfunction "PK2(ADC10/PCINT18)_87") (pintype "bidirectional"))
      (node (ref "IR_8") (pin "3") (pinfunction "3_3") (pintype "passive"))
      (node (ref "IR_LED_8") (pin "1") (pinfunction "1_1") (pintype "passive"))
    )
    (net (code "47") (name "/ISP_MISO") (class "Default")
      (node (ref "IC1") (pin "22") (pinfunction "(MISO/PCINT3)PB3_22") (pintype "bidirectional"))
      (node (ref "ISP") (pin "9") (pinfunction "S_9") (pintype "passive"))
    )
    (net (code "48") (name "/ISP_MOSI") (class "Default")
      (node (ref "IC1") (pin "21") (pinfunction "(MOSI/PCINT2)PB2_21") (pintype "bidirectional"))
      (node (ref "ISP") (pin "1") (pinfunction "S_1") (pintype "passive"))
    )
    (net (code "49") (name "/ISP_SCLK") (class "Default")
      (node (ref "IC1") (pin "20") (pinfunction "(SCK/PCINT1)PB1_20") (pintype "bidirectional"))
      (node (ref "ISP") (pin "7") (pinfunction "S_7") (pintype "passive"))
    )
    (net (code "50") (name "/L1_PA0") (class "Default")
      (node (ref "IC1") (pin "78") (pinfunction "(AD0)PA0_78") (pintype "bidirectional"))
      (node (ref "L293D") (pin "3") (pinfunction "S_3") (pintype "passive"))
    )
    (net (code "51") (name "/L2_PA1") (class "Default")
      (node (ref "IC1") (pin "77") (pinfunction "(AD1)PA1_77") (pintype "bidirectional"))
      (node (ref "L293D") (pin "5") (pinfunction "S_5") (pintype "passive"))
    )
    (net (code "52") (name "/LCD_A") (class "Default")
      (node (ref "LCD_16*4") (pin "15") (pinfunction "A_15") (pintype "power_in"))
      (node (ref "LCD_RES2") (pin "2") (pinfunction "2_2") (pintype "passive"))
    )
    (net (code "53") (name "/LCD_C4") (class "Default")
      (node (ref "IC1") (pin "57") (pinfunction "(A12)PC4_57") (pintype "bidirectional"))
      (node (ref "LCD_16*4") (pin "11") (pinfunction "DB4_11") (pintype "bidirectional"))
    )
    (net (code "54") (name "/LCD_C5") (class "Default")
      (node (ref "IC1") (pin "58") (pinfunction "(A13)PC5_58") (pintype "bidirectional"))
      (node (ref "LCD_16*4") (pin "12") (pinfunction "DB5_12") (pintype "bidirectional"))
    )
    (net (code "55") (name "/LCD_C6") (class "Default")
      (node (ref "IC1") (pin "59") (pinfunction "(A14)PC6_59") (pintype "bidirectional"))
      (node (ref "LCD_16*4") (pin "13") (pinfunction "DB6_13") (pintype "bidirectional"))
    )
    (net (code "56") (name "/LCD_C7") (class "Default")
      (node (ref "IC1") (pin "60") (pinfunction "(A15)PC7_60") (pintype "bidirectional"))
      (node (ref "LCD_16*4") (pin "14") (pinfunction "DB7_14") (pintype "bidirectional"))
    )
    (net (code "57") (name "/LCD_EN_C2") (class "Default")
      (node (ref "IC1") (pin "55") (pinfunction "(A10)PC2_55") (pintype "bidirectional"))
      (node (ref "LCD_16*4") (pin "6") (pinfunction "E_6") (pintype "input"))
    )
    (net (code "58") (name "/LCD_RS_C0") (class "Default")
      (node (ref "IC1") (pin "53") (pinfunction "(A8)PC0_53") (pintype "bidirectional"))
      (node (ref "LCD_16*4") (pin "4") (pinfunction "RS_4") (pintype "input"))
    )
    (net (code "59") (name "/LCD_RW_C1") (class "Default")
      (node (ref "IC1") (pin "54") (pinfunction "(A9)PC1_54") (pintype "bidirectional"))
      (node (ref "LCD_16*4") (pin "5") (pinfunction "R/W_5") (pintype "input"))
    )
    (net (code "60") (name "/MOTOR_SUPPLY") (class "Default")
      (node (ref "C19") (pin "1") (pinfunction "1_1") (pintype "passive"))
      (node (ref "D2") (pin "C") (pinfunction "C_C") (pintype "passive"))
      (node (ref "L293D") (pin "11") (pinfunction "S_11") (pintype "passive"))
    )
    (net (code "61") (name "/MPU_PB0_INT") (class "Default")
      (node (ref "IC1") (pin "19") (pinfunction "(SS/PCINT0)PB0_19") (pintype "bidirectional"))
      (node (ref "MPU_ACC_GYRO") (pin "8") (pinfunction "8_8") (pintype "passive"))
    )
    (net (code "62") (name "/MPU_PD0_SCL") (class "Default")
      (node (ref "10K") (pin "1") (pinfunction "1_1") (pintype "passive"))
      (node (ref "IC1") (pin "43") (pinfunction "(SCL/INT0)PD0_43") (pintype "bidirectional"))
      (node (ref "MPU_ACC_GYRO") (pin "3") (pinfunction "3_3") (pintype "passive"))
    )
    (net (code "63") (name "/MPU_PD1_SDA") (class "Default")
      (node (ref "IC1") (pin "44") (pinfunction "(SDA/INT1)PD1_44") (pintype "bidirectional"))
      (node (ref "MPU_ACC_GYRO") (pin "4") (pinfunction "4_4") (pintype "passive"))
      (node (ref "R9") (pin "1") (pinfunction "1_1") (pintype "passive"))
    )
    (net (code "64") (name "/PB4") (class "Default")
      (node (ref "IC1") (pin "23") (pinfunction "(OC2A/PCINT4)PB4_23") (pintype "bidirectional"))
    )
    (net (code "65") (name "/PD5") (class "Default")
      (node (ref "GPIO") (pin "2") (pinfunction "2_2") (pintype "passive"))
      (node (ref "IC1") (pin "48") (pinfunction "(XCK1)PD5_48") (pintype "bidirectional"))
    )
    (net (code "66") (name "/PD6") (class "Default")
      (node (ref "GPIO") (pin "4") (pinfunction "4_4") (pintype "passive"))
      (node (ref "IC1") (pin "49") (pinfunction "(T1)PD6_49") (pintype "bidirectional"))
    )
    (net (code "67") (name "/PD7") (class "Default")
      (node (ref "GPIO") (pin "6") (pinfunction "6_6") (pintype "passive"))
      (node (ref "IC1") (pin "50") (pinfunction "(T0)PD7_50") (pintype "bidirectional"))
    )
    (net (code "68") (name "/PE2") (class "Default")
      (node (ref "GPIO") (pin "8") (pinfunction "8_8") (pintype "passive"))
      (node (ref "IC1") (pin "4") (pinfunction "(XCK0/AIN0)PE2_4") (pintype "bidirectional"))
    )
    (net (code "69") (name "/PE3") (class "Default")
      (node (ref "GPIO") (pin "10") (pinfunction "10_10") (pintype "passive"))
      (node (ref "IC1") (pin "5") (pinfunction "(OC3A/AIN1)PE3_5") (pintype "bidirectional"))
    )
    (net (code "70") (name "/PE6") (class "Default")
      (node (ref "GPIO") (pin "12") (pinfunction "12_12") (pintype "passive"))
      (node (ref "IC1") (pin "8") (pinfunction "(T3/INT6)PE6_8") (pintype "bidirectional"))
    )
    (net (code "71") (name "/PG0") (class "Default")
      (node (ref "GPIO") (pin "16") (pinfunction "16_16") (pintype "passive"))
      (node (ref "IC1") (pin "51") (pinfunction "(WR)PG0_51") (pintype "bidirectional"))
    )
    (net (code "72") (name "/PG1") (class "Default")
      (node (ref "GPIO") (pin "14") (pinfunction "14_14") (pintype "passive"))
      (node (ref "IC1") (pin "52") (pinfunction "(RD)PG1_52") (pintype "bidirectional"))
    )
    (net (code "73") (name "/PG5") (class "Default")
      (node (ref "GPIO") (pin "18") (pinfunction "18_18") (pintype "passive"))
      (node (ref "IC1") (pin "1") (pinfunction "(OC0B)PG5_1") (pintype "bidirectional"))
    )
    (net (code "74") (name "/PH2") (class "Default")
      (node (ref "GPIO") (pin "20") (pinfunction "20_20") (pintype "passive"))
      (node (ref "IC1") (pin "14") (pinfunction "PH2(XCK2)_14") (pintype "bidirectional"))
    )
    (net (code "75") (name "/PH6") (class "Default")
      (node (ref "GPIO") (pin "21") (pinfunction "21_21") (pintype "passive"))
      (node (ref "IC1") (pin "18") (pinfunction "PH6(OC2B)_18") (pintype "bidirectional"))
    )
    (net (code "76") (name "/PH7") (class "Default")
      (node (ref "GPIO") (pin "19") (pinfunction "19_19") (pintype "passive"))
      (node (ref "IC1") (pin "27") (pinfunction "PH7(T4)_27") (pintype "bidirectional"))
    )
    (net (code "77") (name "/PJ0") (class "Default")
      (node (ref "GPIO") (pin "15") (pinfunction "15_15") (pintype "passive"))
      (node (ref "IC1") (pin "63") (pinfunction "PJ0(RXD3/PCINT9)_63") (pintype "bidirectional"))
    )
    (net (code "78") (name "/PJ1") (class "Default")
      (node (ref "GPIO") (pin "17") (pinfunction "17_17") (pintype "passive"))
      (node (ref "IC1") (pin "64") (pinfunction "PJ1(TXD3/PCINT10)_64") (pintype "bidirectional"))
    )
    (net (code "79") (name "/PK4") (class "Default")
      (node (ref "GPIO") (pin "9") (pinfunction "9_9") (pintype "passive"))
      (node (ref "IC1") (pin "85") (pinfunction "PK4(ADC12/PCINT20)_85") (pintype "bidirectional"))
    )
    (net (code "80") (name "/PK5") (class "Default")
      (node (ref "GPIO") (pin "7") (pinfunction "7_7") (pintype "passive"))
      (node (ref "IC1") (pin "84") (pinfunction "PK5(ADC13/PCINT21)_84") (pintype "bidirectional"))
    )
    (net (code "81") (name "/PK6") (class "Default")
      (node (ref "GPIO") (pin "13") (pinfunction "13_13") (pintype "passive"))
      (node (ref "IC1") (pin "83") (pinfunction "PK6(ADC14/PCINT22)_83") (pintype "bidirectional"))
    )
    (net (code "82") (name "/PK7") (class "Default")
      (node (ref "GPIO") (pin "11") (pinfunction "11_11") (pintype "passive"))
      (node (ref "IC1") (pin "82") (pinfunction "PK7(ADC15/PCINT23)_82") (pintype "bidirectional"))
    )
    (net (code "83") (name "/PWM_L_L3") (class "Default")
      (node (ref "IC1") (pin "38") (pinfunction "PL3(OC5A)_38") (pintype "bidirectional"))
      (node (ref "L293D") (pin "1") (pinfunction "S_1") (pintype "passive"))
    )
    (net (code "84") (name "/PWM_R_L4") (class "Default")
      (node (ref "IC1") (pin "39") (pinfunction "PL4(OC5B)_39") (pintype "bidirectional"))
      (node (ref "L293D") (pin "2") (pinfunction "S_2") (pintype "passive"))
    )
    (net (code "85") (name "/R1_PA2") (class "Default")
      (node (ref "IC1") (pin "76") (pinfunction "(AD2)PA2_76") (pintype "bidirectional"))
      (node (ref "L293D") (pin "4") (pinfunction "S_4") (pintype "passive"))
    )
    (net (code "86") (name "/R2_A3") (class "Default")
      (node (ref "IC1") (pin "75") (pinfunction "(AD3)PA3_75") (pintype "bidirectional"))
      (node (ref "L293D") (pin "6") (pinfunction "S_6") (pintype "passive"))
    )
    (net (code "87") (name "/RESET_30") (class "Default")
      (node (ref "C7") (pin "1") (pinfunction "1_1") (pintype "passive"))
      (node (ref "IC1") (pin "30") (pinfunction "RESET_30") (pintype "input"))
      (node (ref "ISP") (pin "5") (pinfunction "S_5") (pintype "passive"))
      (node (ref "R6") (pin "1") (pinfunction "1_1") (pintype "passive"))
      (node (ref "S3") (pin "1") (pinfunction "S_1") (pintype "passive"))
    )
    (net (code "88") (name "/RTC_PG3") (class "Default")
      (node (ref "IC1") (pin "28") (pinfunction "(TOSC2)PG3_28") (pintype "bidirectional"))
      (node (ref "RTC") (pin "1") (pinfunction "1_1") (pintype "passive"))
    )
    (net (code "89") (name "/RTC_PG4") (class "Default")
      (node (ref "IC1") (pin "29") (pinfunction "(TOSC1)PG4_29") (pintype "bidirectional"))
      (node (ref "RTC") (pin "2") (pinfunction "2_2") (pintype "passive"))
    )
    (net (code "90") (name "/SENSOR_5V") (class "Default")
      (node (ref "10K") (pin "2") (pinfunction "2_2") (pintype "passive"))
      (node (ref "BJT_IR") (pin "C") (pinfunction "C_C") (pintype "passive"))
      (node (ref "BJT_WHITELINE") (pin "C") (pinfunction "C_C") (pintype "passive"))
      (node (ref "C16") (pin "1") (pinfunction "1_1") (pintype "passive"))
      (node (ref "C9") (pin "1") (pinfunction "1_1") (pintype "passive"))
      (node (ref "GPIO") (pin "1") (pinfunction "1_1") (pintype "passive"))
      (node (ref "GPIO") (pin "3") (pinfunction "3_3") (pintype "passive"))
      (node (ref "ISP") (pin "2") (pinfunction "S_2") (pintype "passive"))
      (node (ref "L293D") (pin "7") (pinfunction "S_7") (pintype "passive"))
      (node (ref "LCD_16*4") (pin "2") (pinfunction "VDD_2") (pintype "power_in"))
      (node (ref "LCD_RES1") (pin "E") (pinfunction "E_E") (pintype "passive"))
      (node (ref "LCD_RES2") (pin "1") (pinfunction "1_1") (pintype "passive"))
      (node (ref "LM309H5V") (pin "2") (pinfunction "2_2") (pintype "passive"))
      (node (ref "MPU_ACC_GYRO") (pin "1") (pinfunction "1_1") (pintype "passive"))
      (node (ref "R9") (pin "2") (pinfunction "2_2") (pintype "passive"))
      (node (ref "SERVO_1") (pin "2") (pinfunction "2_2") (pintype "passive"))
      (node (ref "SERVO_2") (pin "2") (pinfunction "2_2") (pintype "passive"))
      (node (ref "SHARP") (pin "3") (pinfunction "3_3") (pintype "passive"))
      (node (ref "SPEAKER") (pin "1") (pinfunction "1_1") (pintype "passive"))
      (node (ref "TSOP_FEMALE") (pin "2") (pinfunction "2_2") (pintype "passive"))
      (node (ref "WHITE_LINE") (pin "1") (pinfunction "S_1") (pintype "passive"))
    )
    (net (code "91") (name "/SERVODATA_B6_1") (class "Default")
      (node (ref "IC1") (pin "25") (pinfunction "(OC1B/PCINT6)PB6_25") (pintype "bidirectional"))
      (node (ref "SERVO_1") (pin "3") (pinfunction "3_3") (pintype "passive"))
    )
    (net (code "92") (name "/SERVODATA_B7_2") (class "Default")
      (node (ref "IC1") (pin "26") (pinfunction "(OC0A/OC1C/PCINT7)PB7_26") (pintype "bidirectional"))
      (node (ref "SERVO_2") (pin "3") (pinfunction "3_3") (pintype "passive"))
    )
    (net (code "93") (name "/SHARP_PK3") (class "Default")
      (node (ref "IC1") (pin "86") (pinfunction "PK3(ADC11/PCINT19)_86") (pintype "bidirectional"))
      (node (ref "SHARP") (pin "1") (pinfunction "1_1") (pintype "passive"))
      (node (ref "SHARP_LED") (pin "A") (pinfunction "A_A") (pintype "passive"))
    )
    (net (code "94") (name "/SYSTEM_5V") (class "Default")
      (node (ref "C14") (pin "1") (pinfunction "1_1") (pintype "passive"))
      (node (ref "C5") (pin "1") (pinfunction "1_1") (pintype "passive"))
      (node (ref "D3") (pin "A") (pinfunction "A_A") (pintype "passive"))
      (node (ref "IC1") (pin "10") (pinfunction "VCC_10") (pintype "power_in"))
      (node (ref "IC1") (pin "100") (pinfunction "AVCC_100") (pintype "power_in"))
      (node (ref "IC1") (pin "31") (pinfunction "VCC1_31") (pintype "power_in"))
      (node (ref "IC1") (pin "61") (pinfunction "VCC2_61") (pintype "power_in"))
      (node (ref "IC1") (pin "80") (pinfunction "VCC3_80") (pintype "power_in"))
      (node (ref "IC1") (pin "98") (pinfunction "AREF_98") (pintype "bidirectional"))
      (node (ref "LM309H") (pin "2") (pinfunction "2_2") (pintype "passive"))
      (node (ref "R5") (pin "1") (pinfunction "1_1") (pintype "passive"))
      (node (ref "R6") (pin "2") (pinfunction "2_2") (pintype "passive"))
    )
    (net (code "95") (name "/TSOP_PE7") (class "Default")
      (node (ref "SJ1") (pin "2") (pinfunction "2_2") (pintype "passive"))
      (node (ref "TSOP_FEMALE") (pin "4") (pinfunction "4_4") (pintype "passive"))
    )
    (net (code "96") (name "/VO") (class "Default")
      (node (ref "LCD_16*4") (pin "3") (pinfunction "VO_3") (pintype "bidirectional"))
      (node (ref "LCD_RES1") (pin "S") (pinfunction "S_S") (pintype "passive"))
    )
    (net (code "97") (name "/VSENSE_K7") (class "Default")
      (node (ref "IC1") (pin "97") (pinfunction "(ADC0)PF0_97") (pintype "bidirectional"))
      (node (ref "LED3") (pin "A") (pinfunction "A_A") (pintype "passive"))
      (node (ref "VSENSE_CAP1") (pin "2") (pinfunction "2_2") (pintype "passive"))
      (node (ref "VSENSE_CAP2") (pin "1") (pinfunction "1_1") (pintype "passive"))
      (node (ref "VSENSE_RES1") (pin "2") (pinfunction "2_2") (pintype "passive"))
      (node (ref "VSENSE_RES2") (pin "1") (pinfunction "1_1") (pintype "passive"))
    )
    (net (code "98") (name "/WHITELINE_BJT") (class "Default")
      (node (ref "BJT_WHITELINE") (pin "E") (pinfunction "E_E") (pintype "passive"))
      (node (ref "WHITE_LINE") (pin "7") (pinfunction "S_7") (pintype "passive"))
    )
    (net (code "99") (name "/WHITELINE_F1_DATA_R") (class "Default")
      (node (ref "IC1") (pin "96") (pinfunction "(ADC1)PF1_96") (pintype "bidirectional"))
      (node (ref "WHITE_LINE") (pin "4") (pinfunction "S_4") (pintype "passive"))
    )
    (net (code "100") (name "/WHITELINE_F2_DATA_C") (class "Default")
      (node (ref "IC1") (pin "95") (pinfunction "(ADC2)PF2_95") (pintype "bidirectional"))
      (node (ref "WHITE_LINE") (pin "2") (pinfunction "S_2") (pintype "passive"))
    )
    (net (code "101") (name "/WHITELINE_F3_DATA_L") (class "Default")
      (node (ref "IC1") (pin "94") (pinfunction "(ADC3)PF3_94") (pintype "bidirectional"))
      (node (ref "WHITE_LINE") (pin "9") (pinfunction "S_9") (pintype "passive"))
    )
    (net (code "102") (name "/WHITELINE_G2_ENABLE") (class "Default")
      (node (ref "BJT_WHITELINE") (pin "B") (pinfunction "B_B") (pintype "passive"))
      (node (ref "IC1") (pin "70") (pinfunction "(ALE)PG2_70") (pintype "bidirectional"))
    )
    (net (code "103") (name "/XBEE_AD3_LED") (class "Default")
      (node (ref "XBEE") (pin "17") (pinfunction "AD3/DIO3_17") (pintype "bidirectional"))
      (node (ref "XBEE_AD3_LED") (pin "A") (pinfunction "A_A") (pintype "passive"))
    )
    (net (code "104") (name "/XBEE_AD5_LED") (class "Default")
      (node (ref "XBEE") (pin "15") (pinfunction "ASC/AD5/DIO5_15") (pintype "bidirectional"))
      (node (ref "XBEE_AD5_LED") (pin "A") (pinfunction "A_A") (pintype "passive"))
    )
    (net (code "105") (name "/XBEE_ON{slash}SLEEP_LED") (class "Default")
      (node (ref "XBEE") (pin "13") (pinfunction "ON/SLEEP_13") (pintype "output"))
      (node (ref "XBEE_ON/SLEEP") (pin "A") (pinfunction "A_A") (pintype "passive"))
    )
    (net (code "106") (name "/XBEE_PE0_DOUT") (class "Default")
      (node (ref "IC1") (pin "2") (pinfunction "(RXD0/PCIN8)PE0_2") (pintype "bidirectional"))
      (node (ref "XBEE") (pin "2") (pinfunction "DOUT_2") (pintype "output"))
    )
    (net (code "107") (name "/XBEE_PE1_DIN") (class "Default")
      (node (ref "IC1") (pin "3") (pinfunction "(TXD0)PE1_3") (pintype "bidirectional"))
      (node (ref "XBEE") (pin "3") (pinfunction "DIN_3") (pintype "input"))
    )
    (net (code "108") (name "/XBEE_PWM0_LED") (class "Default")
      (node (ref "IC1") (pin "35") (pinfunction "PL0(ICP4)_35") (pintype "bidirectional"))
      (node (ref "XBEE") (pin "6") (pinfunction "PWM0/RSSI_6") (pintype "output"))
      (node (ref "XBEE_LED4") (pin "A") (pinfunction "A_A") (pintype "passive"))
    )
    (net (code "109") (name "/XTAL1_34") (class "Default")
      (node (ref "C6") (pin "1") (pinfunction "1_1") (pintype "passive"))
      (node (ref "CRYSTAL") (pin "2") (pinfunction "2_2") (pintype "passive"))
      (node (ref "IC1") (pin "34") (pinfunction "XTAL1_34") (pintype "input"))
    )
    (net (code "110") (name "/XTAL2_33") (class "Default")
      (node (ref "C4") (pin "1") (pinfunction "1_1") (pintype "passive"))
      (node (ref "CRYSTAL") (pin "1") (pinfunction "1_1") (pintype "passive"))
      (node (ref "IC1") (pin "33") (pinfunction "XTAL2_33") (pintype "output"))
    )
    (net (code "111") (name "Net-(BARLED-C)") (class "Default")
      (node (ref "BARLED") (pin "20") (pinfunction "C_20") (pintype "passive"))
      (node (ref "R1") (pin "1") (pinfunction "1_1") (pintype "passive"))
    )
    (net (code "112") (name "Net-(BARLED-C1)") (class "Default")
      (node (ref "BARLED") (pin "19") (pinfunction "C1_19") (pintype "passive"))
      (node (ref "R8") (pin "1") (pinfunction "1_1") (pintype "passive"))
    )
    (net (code "113") (name "Net-(BARLED-C2)") (class "Default")
      (node (ref "BARLED") (pin "18") (pinfunction "C2_18") (pintype "passive"))
      (node (ref "R10") (pin "1") (pinfunction "1_1") (pintype "passive"))
    )
    (net (code "114") (name "Net-(BARLED-C3)") (class "Default")
      (node (ref "BARLED") (pin "17") (pinfunction "C3_17") (pintype "passive"))
      (node (ref "R11") (pin "1") (pinfunction "1_1") (pintype "passive"))
    )
    (net (code "115") (name "Net-(BARLED-C4)") (class "Default")
      (node (ref "BARLED") (pin "16") (pinfunction "C4_16") (pintype "passive"))
      (node (ref "R12") (pin "1") (pinfunction "1_1") (pintype "passive"))
    )
    (net (code "116") (name "Net-(BARLED-C5)") (class "Default")
      (node (ref "BARLED") (pin "15") (pinfunction "C5_15") (pintype "passive"))
      (node (ref "R13") (pin "1") (pinfunction "1_1") (pintype "passive"))
    )
    (net (code "117") (name "Net-(BARLED-C6)") (class "Default")
      (node (ref "BARLED") (pin "14") (pinfunction "C6_14") (pintype "passive"))
      (node (ref "R14") (pin "1") (pinfunction "1_1") (pintype "passive"))
    )
    (net (code "118") (name "Net-(BARLED-C7)") (class "Default")
      (node (ref "BARLED") (pin "13") (pinfunction "C7_13") (pintype "passive"))
      (node (ref "R15") (pin "1") (pinfunction "1_1") (pintype "passive"))
    )
    (net (code "119") (name "Net-(BARLED-C8)") (class "Default")
      (node (ref "BARLED") (pin "12") (pinfunction "C8_12") (pintype "passive"))
      (node (ref "R16") (pin "1") (pinfunction "1_1") (pintype "passive"))
    )
    (net (code "120") (name "Net-(BARLED-C9)") (class "Default")
      (node (ref "BARLED") (pin "11") (pinfunction "C9_11") (pintype "passive"))
      (node (ref "R17") (pin "1") (pinfunction "1_1") (pintype "passive"))
    )
    (net (code "121") (name "Net-(C12-Pad1)") (class "Default")
      (node (ref "C12") (pin "1") (pinfunction "1_1") (pintype "passive"))
      (node (ref "C13") (pin "1") (pinfunction "1_1") (pintype "passive"))
      (node (ref "C15") (pin "1") (pinfunction "1_1") (pintype "passive"))
      (node (ref "C18") (pin "1") (pinfunction "1_1") (pintype "passive"))
      (node (ref "D1") (pin "C") (pinfunction "C_C") (pintype "passive"))
      (node (ref "LM309H") (pin "1") (pinfunction "1_1") (pintype "passive"))
      (node (ref "LM309H5V") (pin "1") (pinfunction "1_1") (pintype "passive"))
      (node (ref "LM3940") (pin "1") (pinfunction "1_1") (pintype "passive"))
    )
    (net (code "122") (name "Net-(D3-PadC)") (class "Default")
      (node (ref "D3") (pin "C") (pinfunction "C_C") (pintype "passive"))
      (node (ref "R2") (pin "2") (pinfunction "2_2") (pintype "passive"))
    )
    (net (code "123") (name "Net-(IR_DATA_1-PadA)") (class "Default")
      (node (ref "IR_DATA_1") (pin "A") (pinfunction "A_A") (pintype "passive"))
      (node (ref "IR_LED1") (pin "2") (pinfunction "2_2") (pintype "passive"))
    )
    (net (code "124") (name "Net-(IR_DATA_2-PadA)") (class "Default")
      (node (ref "IR_DATA_2") (pin "A") (pinfunction "A_A") (pintype "passive"))
      (node (ref "IR_LED2") (pin "2") (pinfunction "2_2") (pintype "passive"))
    )
    (net (code "125") (name "Net-(IR_DATA_4-PadA)") (class "Default")
      (node (ref "IR_DATA_4") (pin "A") (pinfunction "A_A") (pintype "passive"))
      (node (ref "IR_LED4") (pin "2") (pinfunction "2_2") (pintype "passive"))
    )
    (net (code "126") (name "Net-(IR_DATA_5-PadA)") (class "Default")
      (node (ref "IR_DATA_5") (pin "A") (pinfunction "A_A") (pintype "passive"))
      (node (ref "IR_LED5") (pin "2") (pinfunction "2_2") (pintype "passive"))
    )
    (net (code "127") (name "Net-(IR_DATA_6-PadA)") (class "Default")
      (node (ref "IR_DATA_6") (pin "A") (pinfunction "A_A") (pintype "passive"))
      (node (ref "IR_LED6") (pin "2") (pinfunction "2_2") (pintype "passive"))
    )
    (net (code "128") (name "Net-(IR_DATA_7-PadA)") (class "Default")
      (node (ref "IR_DATA_7") (pin "A") (pinfunction "A_A") (pintype "passive"))
      (node (ref "IR_LED7") (pin "2") (pinfunction "2_2") (pintype "passive"))
    )
    (net (code "129") (name "Net-(IR_DATA_8-PadA)") (class "Default")
      (node (ref "IR_DATA_8") (pin "A") (pinfunction "A_A") (pintype "passive"))
      (node (ref "IR_LED_8") (pin "2") (pinfunction "2_2") (pintype "passive"))
    )
    (net (code "130") (name "Net-(LED1-PadC)") (class "Default")
      (node (ref "LED1") (pin "C") (pinfunction "C_C") (pintype "passive"))
      (node (ref "R3") (pin "1") (pinfunction "1_1") (pintype "passive"))
    )
    (net (code "131") (name "Net-(LED2-PadC)") (class "Default")
      (node (ref "LED2") (pin "C") (pinfunction "C_C") (pintype "passive"))
      (node (ref "R4") (pin "1") (pinfunction "1_1") (pintype "passive"))
    )
    (net (code "132") (name "Net-(LED3-PadC)") (class "Default")
      (node (ref "LED3") (pin "C") (pinfunction "C_C") (pintype "passive"))
      (node (ref "R7") (pin "1") (pinfunction "1_1") (pintype "passive"))
    )
    (net (code "133") (name "Net-(POWERSWITCH-P)") (class "Default")
      (node (ref "D1") (pin "A") (pinfunction "A_A") (pintype "passive"))
      (node (ref "D2") (pin "A") (pinfunction "A_A") (pintype "passive"))
      (node (ref "POWERSWITCH") (pin "2") (pinfunction "P_2") (pintype "passive"))
    )
    (net (code "134") (name "Net-(SHARP_LED-PadC)") (class "Default")
      (node (ref "SHARP_LED") (pin "C") (pinfunction "C_C") (pintype "passive"))
      (node (ref "SHARP_RES") (pin "2") (pinfunction "2_2") (pintype "passive"))
    )
    (net (code "135") (name "Net-(XBEE_AD3_LED-PadC)") (class "Default")
      (node (ref "XBEE_AD3_LED") (pin "C") (pinfunction "C_C") (pintype "passive"))
      (node (ref "XBEE_RES1") (pin "2") (pinfunction "2_2") (pintype "passive"))
    )
    (net (code "136") (name "Net-(XBEE_AD5_LED-PadC)") (class "Default")
      (node (ref "XBEE_AD5_LED") (pin "C") (pinfunction "C_C") (pintype "passive"))
      (node (ref "XBEE_RES2") (pin "2") (pinfunction "2_2") (pintype "passive"))
    )
    (net (code "137") (name "Net-(XBEE_LED4-PadC)") (class "Default")
      (node (ref "XBEE_LED4") (pin "C") (pinfunction "C_C") (pintype "passive"))
      (node (ref "XBEE_RES4") (pin "2") (pinfunction "2_2") (pintype "passive"))
    )
    (net (code "138") (name "Net-(XBEE_ON/SLEEP-PadC)") (class "Default")
      (node (ref "XBEE_ON/SLEEP") (pin "C") (pinfunction "C_C") (pintype "passive"))
      (node (ref "XBEE_RES3") (pin "2") (pinfunction "2_2") (pintype "passive"))
    )
    (net (code "139") (name "unconnected-(FT232_USB_TYPEC-3V3OUT-Pad17)") (class "Default")
      (node (ref "FT232_USB_TYPEC") (pin "17") (pinfunction "3V3OUT_17") (pintype "output"))
    )
    (net (code "140") (name "unconnected-(FT232_USB_TYPEC-CBUS2-Pad13)") (class "Default")
      (node (ref "FT232_USB_TYPEC") (pin "13") (pinfunction "CBUS2_13") (pintype "bidirectional"))
    )
    (net (code "141") (name "unconnected-(FT232_USB_TYPEC-CBUS3-Pad14)") (class "Default")
      (node (ref "FT232_USB_TYPEC") (pin "14") (pinfunction "CBUS3_14") (pintype "bidirectional"))
    )
    (net (code "142") (name "unconnected-(FT232_USB_TYPEC-CBUS4-Pad12)") (class "Default")
      (node (ref "FT232_USB_TYPEC") (pin "12") (pinfunction "CBUS4_12") (pintype "bidirectional"))
    )
    (net (code "143") (name "unconnected-(FT232_USB_TYPEC-OSCI-Pad27)") (class "Default")
      (node (ref "FT232_USB_TYPEC") (pin "27") (pinfunction "OSCI_27") (pintype "input"))
    )
    (net (code "144") (name "unconnected-(FT232_USB_TYPEC-OSCO-Pad28)") (class "Default")
      (node (ref "FT232_USB_TYPEC") (pin "28") (pinfunction "OSCO_28") (pintype "output"))
    )
    (net (code "145") (name "unconnected-(FT232_USB_TYPEC-~{CTS}-Pad11)") (class "Default")
      (node (ref "FT232_USB_TYPEC") (pin "11") (pinfunction "~{CTS}_11") (pintype "input"))
    )
    (net (code "146") (name "unconnected-(FT232_USB_TYPEC-~{DCD}-Pad10)") (class "Default")
      (node (ref "FT232_USB_TYPEC") (pin "10") (pinfunction "~{DCD}_10") (pintype "input"))
    )
    (net (code "147") (name "unconnected-(FT232_USB_TYPEC-~{DSR}-Pad9)") (class "Default")
      (node (ref "FT232_USB_TYPEC") (pin "9") (pinfunction "~{DSR}_9") (pintype "input"))
    )
    (net (code "148") (name "unconnected-(FT232_USB_TYPEC-~{DTR}-Pad2)") (class "Default")
      (node (ref "FT232_USB_TYPEC") (pin "2") (pinfunction "~{DTR}_2") (pintype "output"))
    )
    (net (code "149") (name "unconnected-(FT232_USB_TYPEC-~{RESET}-Pad19)") (class "Default")
      (node (ref "FT232_USB_TYPEC") (pin "19") (pinfunction "~{RESET}_19") (pintype "input"))
    )
    (net (code "150") (name "unconnected-(FT232_USB_TYPEC-~{RI}-Pad6)") (class "Default")
      (node (ref "FT232_USB_TYPEC") (pin "6") (pinfunction "~{RI}_6") (pintype "input"))
    )
    (net (code "151") (name "unconnected-(FT232_USB_TYPEC-~{RTS}-Pad3)") (class "Default")
      (node (ref "FT232_USB_TYPEC") (pin "3") (pinfunction "~{RTS}_3") (pintype "output"))
    )
    (net (code "152") (name "unconnected-(ISPD-S-Pad3)") (class "Default")
      (node (ref "ISP") (pin "3") (pinfunction "S_3") (pintype "passive"))
    )
    (net (code "153") (name "unconnected-(LCD_16*4-DB0-Pad7)") (class "Default")
      (node (ref "LCD_16*4") (pin "7") (pinfunction "DB0_7") (pintype "bidirectional"))
    )
    (net (code "154") (name "unconnected-(LCD_16*4-DB1-Pad8)") (class "Default")
      (node (ref "LCD_16*4") (pin "8") (pinfunction "DB1_8") (pintype "bidirectional"))
    )
    (net (code "155") (name "unconnected-(LCD_16*4-DB2-Pad9)") (class "Default")
      (node (ref "LCD_16*4") (pin "9") (pinfunction "DB2_9") (pintype "bidirectional"))
    )
    (net (code "156") (name "unconnected-(LCD_16*4-DB3-Pad10)") (class "Default")
      (node (ref "LCD_16*4") (pin "10") (pinfunction "DB3_10") (pintype "bidirectional"))
    )
    (net (code "157") (name "unconnected-(MPU_ACC_GYRO-Pad5)") (class "Default")
      (node (ref "MPU_ACC_GYRO") (pin "5") (pinfunction "5_5") (pintype "passive"))
    )
    (net (code "158") (name "unconnected-(MPU_ACC_GYRO-Pad6)") (class "Default")
      (node (ref "MPU_ACC_GYRO") (pin "6") (pinfunction "6_6") (pintype "passive"))
    )
    (net (code "159") (name "unconnected-(MPU_ACC_GYRO-Pad7)") (class "Default")
      (node (ref "MPU_ACC_GYRO") (pin "7") (pinfunction "7_7") (pintype "passive"))
    )
    (net (code "160") (name "unconnected-(S1-P1-Pad4)") (class "Default")
      (node (ref "S1") (pin "4") (pinfunction "P1_4") (pintype "passive"))
    )
    (net (code "161") (name "unconnected-(S1-S1-Pad2)") (class "Default")
      (node (ref "S1") (pin "2") (pinfunction "S1_2") (pintype "passive"))
    )
    (net (code "162") (name "unconnected-(S3-P1-Pad4)") (class "Default")
      (node (ref "S3") (pin "4") (pinfunction "P1_4") (pintype "passive"))
    )
    (net (code "163") (name "unconnected-(S3-S1-Pad2)") (class "Default")
      (node (ref "S3") (pin "2") (pinfunction "S1_2") (pintype "passive"))
    )
    (net (code "164") (name "unconnected-(TSOP_FEMALE-Pad3)") (class "Default")
      (node (ref "TSOP_FEMALE") (pin "3") (pinfunction "3_3") (pintype "passive"))
    )
    (net (code "165") (name "unconnected-(WHITE_LINEB-S-Pad10)") (class "Default")
      (node (ref "WHITE_LINE") (pin "10") (pinfunction "S_10") (pintype "passive"))
    )
    (net (code "166") (name "unconnected-(WHITE_LINEG-S-Pad6)") (class "Default")
      (node (ref "WHITE_LINE") (pin "6") (pinfunction "S_6") (pintype "passive"))
    )
    (net (code "167") (name "unconnected-(WHITE_LINEI-S-Pad8)") (class "Default")
      (node (ref "WHITE_LINE") (pin "8") (pinfunction "S_8") (pintype "passive"))
    )
    (net (code "168") (name "unconnected-(XBEE-AD0{slash}DIO0-Pad20)") (class "Default")
      (node (ref "XBEE") (pin "20") (pinfunction "AD0/DIO0_20") (pintype "bidirectional"))
    )
    (net (code "169") (name "unconnected-(XBEE-AD1{slash}DIO1-Pad19)") (class "Default")
      (node (ref "XBEE") (pin "19") (pinfunction "AD1/DIO1_19") (pintype "bidirectional"))
    )
    (net (code "170") (name "unconnected-(XBEE-AD2{slash}DIO2-Pad18)") (class "Default")
      (node (ref "XBEE") (pin "18") (pinfunction "AD2/DIO2_18") (pintype "bidirectional"))
    )
    (net (code "171") (name "unconnected-(XBEE-AD4{slash}DIO4-Pad11)") (class "Default")
      (node (ref "XBEE") (pin "11") (pinfunction "AD4/DIO4_11") (pintype "bidirectional"))
    )
    (net (code "172") (name "unconnected-(XBEE-CTS{slash}DIO7-Pad12)") (class "Default")
      (node (ref "XBEE") (pin "12") (pinfunction "CTS/DIO7_12") (pintype "bidirectional"))
    )
    (net (code "173") (name "unconnected-(XBEE-DO8-Pad4)") (class "Default")
      (node (ref "XBEE") (pin "4") (pinfunction "DO8_4") (pintype "output"))
    )
    (net (code "174") (name "unconnected-(XBEE-DTR{slash}DI8-Pad9)") (class "Default")
      (node (ref "XBEE") (pin "9") (pinfunction "DTR/DI8_9") (pintype "input"))
    )
    (net (code "175") (name "unconnected-(XBEE-PWM1-Pad7)") (class "Default")
      (node (ref "XBEE") (pin "7") (pinfunction "PWM1_7") (pintype "output"))
    )
    (net (code "176") (name "unconnected-(XBEE-RESERVED-Pad8)") (class "Default")
      (node (ref "XBEE") (pin "8") (pinfunction "RESERVED_8") (pintype "no_connect"))
    )
    (net (code "177") (name "unconnected-(XBEE-RESET-Pad5)") (class "Default")
      (node (ref "XBEE") (pin "5") (pinfunction "RESET_5") (pintype "input"))
    )
    (net (code "178") (name "unconnected-(XBEE-RTS{slash}AD6{slash}DIO6-Pad16)") (class "Default")
      (node (ref "XBEE") (pin "16") (pinfunction "RTS/AD6/DIO6_16") (pintype "bidirectional"))
    )
    (net (code "179") (name "unconnected-(XBEE-VREF-Pad14)") (class "Default")
      (node (ref "XBEE") (pin "14") (pinfunction "VREF_14") (pintype "input"))
    )
  )
)
